# Sheet1.net
KiCad netlist of a schematic drawn in Altium Designer
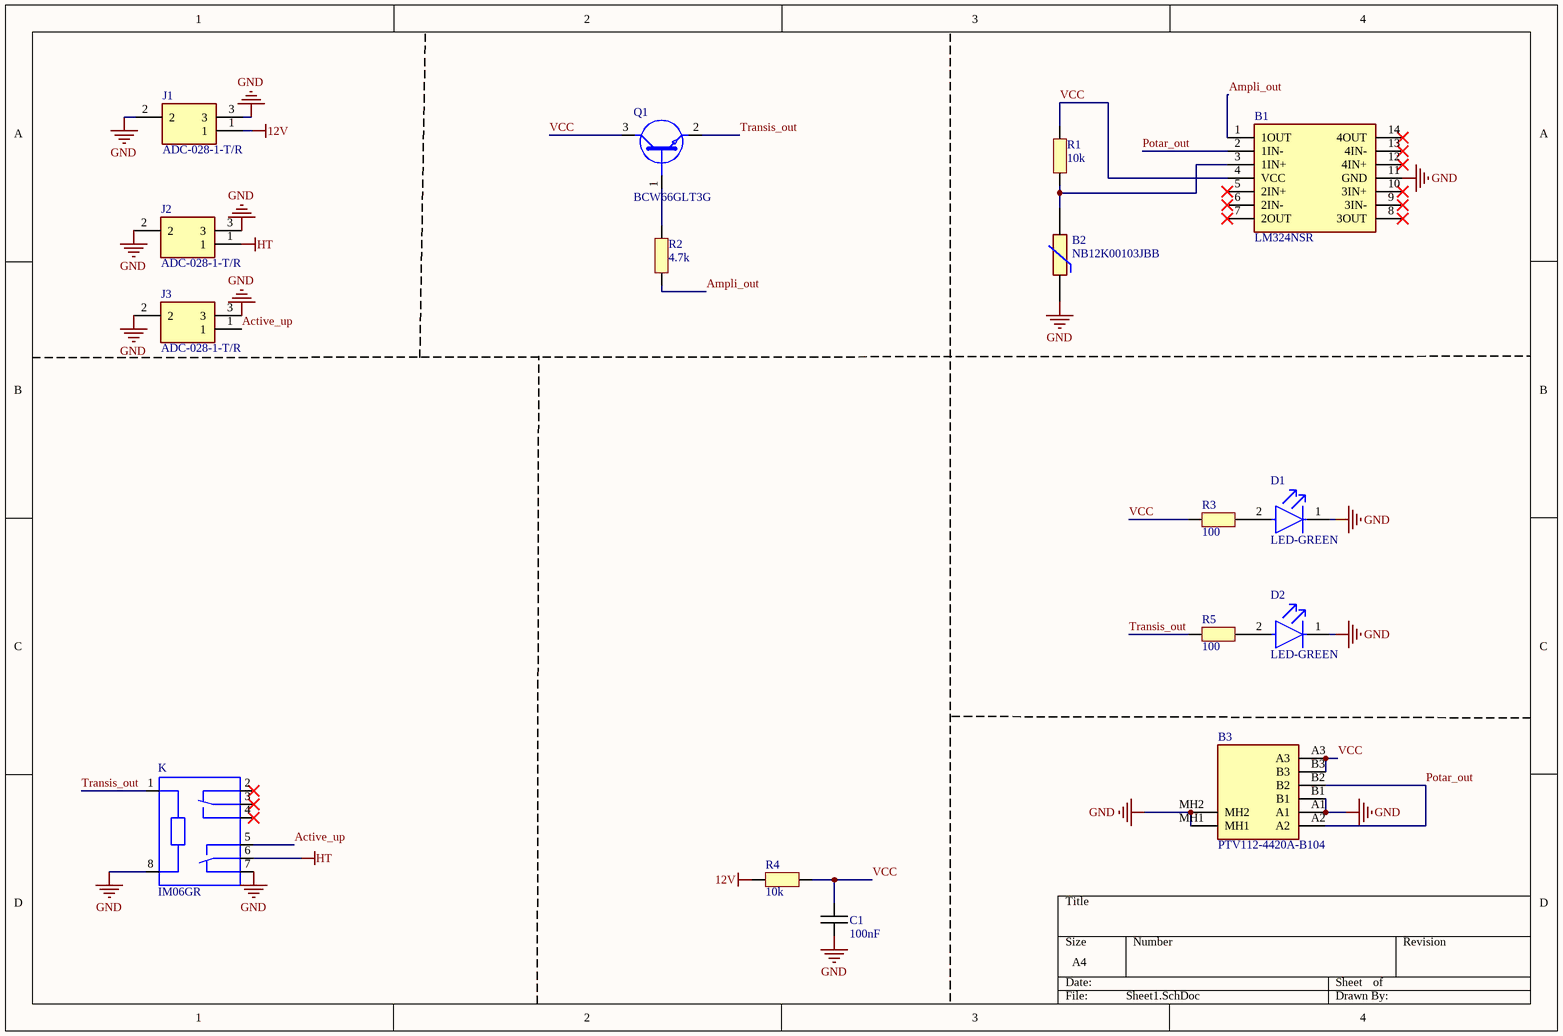
[diagram p0: Sheet1.SchDoc]

(export (version "E")
  (design (tool "Eeschema 10.0.6"))
  (components
    (comp (ref "B1")
      (value "LM324NSR")
      (footprint "SOIC127P780X200-14N")
      (description "Quadruple Operational Amplifier")
      (fields (field (name "MOUSER PART NUMBER") "595-LM324NSR"))
      (libsource (lib "Schlib1") (part "LM324NSR"))
    )
    (comp (ref "B2")
      (value "NB12K00103JBB")
      (footprint "RESC2212X50N")
      (description "NTC SMD Thermistor, NB12K, 10K, 5% AVX 10k 0805 Protection NTC Thermistor, 5s, 2 x 1.25 x 1.3mm")
      (fields (field (name "MOUSER PART NUMBER") "581-NB12K00103JBB"))
      (libsource (lib "Schlib1") (part "NB12K00103JBB"))
    )
    (comp (ref "B3")
      (value "PTV112-4420A-B104")
      (footprint "PTV1124420AB104")
      (description "Potentiometers PANEL CONTROL 100kOhm")
      (fields (field (name "MOUSER PART NUMBER") "652-PTV1124420AB104"))
      (libsource (lib "Schlib1") (part "PTV112-4420A-B104"))
    )
    (comp (ref "C1")
      (value "100nF")
      (footprint "CAPC1005X06N")
      (libsource (lib "Schlib1") (part "Capacitor"))
    )
    (comp (ref "D1")
      (value "LED-GREEN")
      (footprint "SMD-1608-LED")
      (description "LED GREEN CLEAR CHIP SMD LTST-C190GKT")
      (fields (field (name "VOLTAGE") "2V"))
      (libsource (lib "Schlib1") (part "LED-GREEN"))
    )
    (comp (ref "D2")
      (value "LED-GREEN")
      (footprint "SMD-1608-LED")
      (description "LED GREEN CLEAR CHIP SMD LTST-C190GKT")
      (fields (field (name "VOLTAGE") "2V"))
      (libsource (lib "Schlib1") (part "LED-GREEN"))
    )
    (comp (ref "J1")
      (value "ADC-028-1-T/R")
      (footprint "PJ1021SMTTR")
      (description "Connecteurs d'alimentation continue DC POWER JACK 2MM PIN TYPE 028")
      (fields (field (name "MOUSER PART NUMBER") "737-ADC-028-1-T/R"))
      (libsource (lib "Schlib1") (part "ADC-028-1-T/R"))
    )
    (comp (ref "J2")
      (value "ADC-028-1-T/R")
      (footprint "PJ1021SMTTR")
      (description "Connecteurs d'alimentation continue DC POWER JACK 2MM PIN TYPE 028")
      (fields (field (name "MOUSER PART NUMBER") "737-ADC-028-1-T/R"))
      (libsource (lib "Schlib1") (part "ADC-028-1-T/R"))
    )
    (comp (ref "J3")
      (value "ADC-028-1-T/R")
      (footprint "PJ1021SMTTR")
      (description "Connecteurs d'alimentation continue DC POWER JACK 2MM PIN TYPE 028")
      (fields (field (name "MOUSER PART NUMBER") "737-ADC-028-1-T/R"))
      (libsource (lib "Schlib1") (part "ADC-028-1-T/R"))
    )
    (comp (ref "K")
      (value "IM06GR")
      (footprint "RELAY_IM06GR")
      (description "Electromechanical Relay 12VDC 1.029KOhm 2A DPDT _10x7.5x5.65_mm SMD Signal Relay")
      (fields (field (name "MF") "TE Connectivity"))
      (libsource (lib "Schlib1") (part "IM06GR"))
    )
    (comp (ref "Q1")
      (value "BCW66GLT3G")
      (footprint "SOT96P237X111-3N")
      (description "NPN Bipolar Transistor")
      (fields (field (name "MOUSER PART NUMBER") "863-BCW66GLT3G"))
      (libsource (lib "Schlib1") (part "BCW66GLT3G"))
    )
    (comp (ref "R1") (value "10k") (footprint "RESC1005X06N") (libsource (lib "") (part "Resistor_1")))
    (comp (ref "R2") (value "4.7k") (footprint "RESC1005X06N") (libsource (lib "") (part "Resistor_1")))
    (comp (ref "R3") (value "100") (footprint "RESC1005X06N") (libsource (lib "Schlib1") (part "Resistor")))
    (comp (ref "R4") (value "10k") (footprint "RESC1005X06N") (libsource (lib "Schlib1") (part "Resistor")))
    (comp (ref "R5") (value "100") (footprint "RESC1005X06N") (libsource (lib "Schlib1") (part "Resistor")))
  )
  (nets
    (net (code "1") (name "/Active_up") (class "Default")
      (node (ref "J3") (pin "1") (pinfunction "1_1") (pintype "passive"))
      (node (ref "K") (pin "5") (pinfunction "5_5") (pintype "passive"))
    )
    (net (code "2") (name "/Ampli_out") (class "Default")
      (node (ref "B1") (pin "1") (pinfunction "1OUT_1") (pintype "passive"))
      (node (ref "R2") (pin "1") (pinfunction "1_1") (pintype "passive"))
    )
    (net (code "3") (name "/Potar_out") (class "Default")
      (node (ref "B1") (pin "2") (pinfunction "1IN-_2") (pintype "passive"))
      (node (ref "B3") (pin "A2") (pinfunction "A2_A2") (pintype "passive"))
      (node (ref "B3") (pin "B2") (pinfunction "B2_B2") (pintype "passive"))
    )
    (net (code "4") (name "/Transis_out") (class "Default")
      (node (ref "K") (pin "1") (pinfunction "1_1") (pintype "passive"))
      (node (ref "Q1") (pin "2") (pinfunction "E_2") (pintype "passive"))
      (node (ref "R5") (pin "1") (pinfunction "1_1") (pintype "passive"))
    )
    (net (code "5") (name "/VCC") (class "Default")
      (node (ref "B1") (pin "4") (pinfunction "VCC_4") (pintype "passive"))
      (node (ref "B3") (pin "A3") (pinfunction "A3_A3") (pintype "passive"))
      (node (ref "B3") (pin "B3") (pinfunction "B3_B3") (pintype "passive"))
      (node (ref "C1") (pin "1") (pinfunction "1_1") (pintype "passive"))
      (node (ref "Q1") (pin "3") (pinfunction "C_3") (pintype "passive"))
      (node (ref "R1") (pin "2") (pinfunction "2_2") (pintype "passive"))
      (node (ref "R3") (pin "1") (pinfunction "1_1") (pintype "passive"))
      (node (ref "R4") (pin "2") (pinfunction "2_2") (pintype "passive"))
    )
    (net (code "6") (name "12V") (class "Default")
      (node (ref "J1") (pin "1") (pinfunction "1_1") (pintype "passive"))
      (node (ref "R4") (pin "1") (pinfunction "1_1") (pintype "passive"))
    )
    (net (code "7") (name "GND") (class "Default")
      (node (ref "B1") (pin "11") (pinfunction "GND_11") (pintype "passive"))
      (node (ref "B2") (pin "1") (pinfunction "1_1") (pintype "passive"))
      (node (ref "B3") (pin "A1") (pinfunction "A1_A1") (pintype "passive"))
      (node (ref "B3") (pin "B1") (pinfunction "B1_B1") (pintype "passive"))
      (node (ref "B3") (pin "MH1") (pinfunction "MH1_MH1") (pintype "passive"))
      (node (ref "B3") (pin "MH2") (pinfunction "MH2_MH2") (pintype "passive"))
      (node (ref "C1") (pin "2") (pinfunction "2_2") (pintype "passive"))
      (node (ref "D1") (pin "1") (pinfunction "C_1") (pintype "passive"))
      (node (ref "D2") (pin "1") (pinfunction "C_1") (pintype "passive"))
      (node (ref "J1") (pin "2") (pinfunction "2_2") (pintype "passive"))
      (node (ref "J1") (pin "3") (pinfunction "3_3") (pintype "passive"))
      (node (ref "J2") (pin "2") (pinfunction "2_2") (pintype "passive"))
      (node (ref "J2") (pin "3") (pinfunction "3_3") (pintype "passive"))
      (node (ref "J3") (pin "2") (pinfunction "2_2") (pintype "passive"))
      (node (ref "J3") (pin "3") (pinfunction "3_3") (pintype "passive"))
      (node (ref "K") (pin "7") (pinfunction "7_7") (pintype "passive"))
      (node (ref "K") (pin "8") (pinfunction "8_8") (pintype "passive"))
    )
    (net (code "8") (name "HT") (class "Default")
      (node (ref "J2") (pin "1") (pinfunction "1_1") (pintype "passive"))
      (node (ref "K") (pin "6") (pinfunction "6_6") (pintype "passive"))
    )
    (net (code "9") (name "Net-(B1-1IN+)") (class "Default")
      (node (ref "B1") (pin "3") (pinfunction "1IN+_3") (pintype "passive"))
      (node (ref "B2") (pin "2") (pinfunction "2_2") (pintype "passive"))
      (node (ref "R1") (pin "1") (pinfunction "1_1") (pintype "passive"))
    )
    (net (code "10") (name "Net-(D1-A)") (class "Default")
      (node (ref "D1") (pin "2") (pinfunction "A_2") (pintype "passive"))
      (node (ref "R3") (pin "2") (pinfunction "2_2") (pintype "passive"))
    )
    (net (code "11") (name "Net-(D2-A)") (class "Default")
      (node (ref "D2") (pin "2") (pinfunction "A_2") (pintype "passive"))
      (node (ref "R5") (pin "2") (pinfunction "2_2") (pintype "passive"))
    )
    (net (code "12") (name "Net-(Q1-B)") (class "Default")
      (node (ref "Q1") (pin "1") (pinfunction "B_1") (pintype "passive"))
      (node (ref "R2") (pin "2") (pinfunction "2_2") (pintype "passive"))
    )
    (net (code "13") (name "unconnected-(B1-2IN+-Pad5)") (class "Default")
      (node (ref "B1") (pin "5") (pinfunction "2IN+_5") (pintype "passive+no_connect"))
    )
    (net (code "14") (name "unconnected-(B1-2IN--Pad6)") (class "Default")
      (node (ref "B1") (pin "6") (pinfunction "2IN-_6") (pintype "passive+no_connect"))
    )
    (net (code "15") (name "unconnected-(B1-2OUT-Pad7)") (class "Default")
      (node (ref "B1") (pin "7") (pinfunction "2OUT_7") (pintype "passive+no_connect"))
    )
    (net (code "16") (name "unconnected-(B1-3IN+-Pad10)") (class "Default")
      (node (ref "B1") (pin "10") (pinfunction "3IN+_10") (pintype "passive+no_connect"))
    )
    (net (code "17") (name "unconnected-(B1-3IN--Pad9)") (class "Default")
      (node (ref "B1") (pin "9") (pinfunction "3IN-_9") (pintype "passive+no_connect"))
    )
    (net (code "18") (name "unconnected-(B1-3OUT-Pad8)") (class "Default")
      (node (ref "B1") (pin "8") (pinfunction "3OUT_8") (pintype "passive+no_connect"))
    )
    (net (code "19") (name "unconnected-(B1-4IN+-Pad12)") (class "Default")
      (node (ref "B1") (pin "12") (pinfunction "4IN+_12") (pintype "passive+no_connect"))
    )
    (net (code "20") (name "unconnected-(B1-4IN--Pad13)") (class "Default")
      (node (ref "B1") (pin "13") (pinfunction "4IN-_13") (pintype "passive+no_connect"))
    )
    (net (code "21") (name "unconnected-(B1-4OUT-Pad14)") (class "Default")
      (node (ref "B1") (pin "14") (pinfunction "4OUT_14") (pintype "passive+no_connect"))
    )
    (net (code "22") (name "unconnected-(K-Pad2)") (class "Default")
      (node (ref "K") (pin "2") (pinfunction "2_2") (pintype "passive+no_connect"))
    )
    (net (code "23") (name "unconnected-(K-Pad3)") (class "Default")
      (node (ref "K") (pin "3") (pinfunction "3_3") (pintype "passive+no_connect"))
    )
    (net (code "24") (name "unconnected-(K-Pad4)") (class "Default")
      (node (ref "K") (pin "4") (pinfunction "4_4") (pintype "passive+no_connect"))
    )
  )
)
